# uc2C.net
KiCad netlist of a schematic drawn in Altium Designer
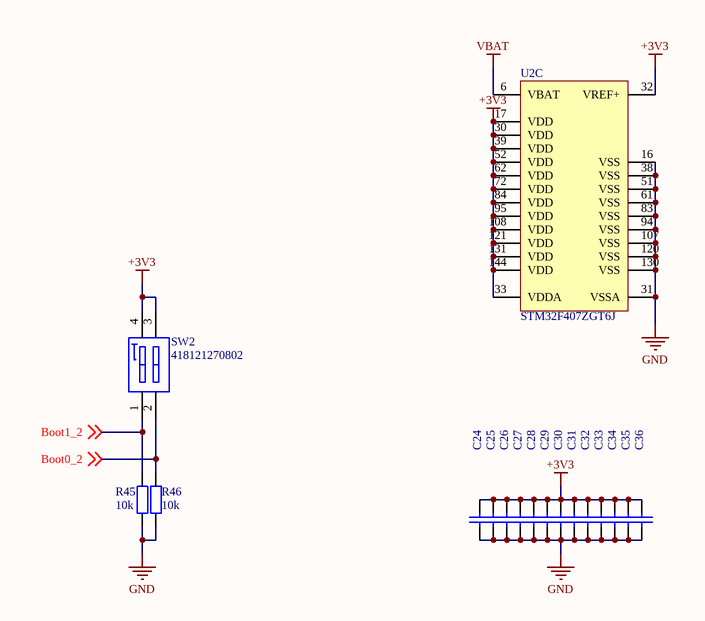
[diagram p0: uc2C.SchDoc]

(export (version "E")
  (design (tool "Eeschema 10.0.6"))
  (components
    (comp (ref "C24")
      (value "100nF")
      (footprint "C2012")
      (description "Capacitor")
      (fields
        (field (name "MANUFACTURER") "MULTICOMP")
        (field (name "MANUFACTURER PART NUMBER") "MC0805B104K500CT")
        (field (name "PUBLISHER") "Altium Limited")
      )
      (libsource (lib "Miscellaneous Devices") (part "Cap"))
    )
    (comp (ref "C25")
      (value "100nF")
      (footprint "C2012")
      (description "Capacitor")
      (fields
        (field (name "MANUFACTURER") "MULTICOMP")
        (field (name "MANUFACTURER PART NUMBER") "MC0805B104K500CT")
        (field (name "PUBLISHER") "Altium Limited")
      )
      (libsource (lib "Miscellaneous Devices") (part "Cap"))
    )
    (comp (ref "C26")
      (value "100nF")
      (footprint "C2012")
      (description "Capacitor")
      (fields
        (field (name "MANUFACTURER") "MULTICOMP")
        (field (name "MANUFACTURER PART NUMBER") "MC0805B104K500CT")
        (field (name "PUBLISHER") "Altium Limited")
      )
      (libsource (lib "Miscellaneous Devices") (part "Cap"))
    )
    (comp (ref "C27")
      (value "100nF")
      (footprint "C2012")
      (description "Capacitor")
      (fields
        (field (name "MANUFACTURER") "MULTICOMP")
        (field (name "MANUFACTURER PART NUMBER") "MC0805B104K500CT")
        (field (name "PUBLISHER") "Altium Limited")
      )
      (libsource (lib "Miscellaneous Devices") (part "Cap"))
    )
    (comp (ref "C28")
      (value "100nF")
      (footprint "C2012")
      (description "Capacitor")
      (fields
        (field (name "MANUFACTURER") "MULTICOMP")
        (field (name "MANUFACTURER PART NUMBER") "MC0805B104K500CT")
        (field (name "PUBLISHER") "Altium Limited")
      )
      (libsource (lib "Miscellaneous Devices") (part "Cap"))
    )
    (comp (ref "C29")
      (value "100nF")
      (footprint "C2012")
      (description "Capacitor")
      (fields
        (field (name "MANUFACTURER") "MULTICOMP")
        (field (name "MANUFACTURER PART NUMBER") "MC0805B104K500CT")
        (field (name "PUBLISHER") "Altium Limited")
      )
      (libsource (lib "Miscellaneous Devices") (part "Cap"))
    )
    (comp (ref "C30")
      (value "100nF")
      (footprint "C2012")
      (description "Capacitor")
      (fields
        (field (name "MANUFACTURER") "MULTICOMP")
        (field (name "MANUFACTURER PART NUMBER") "MC0805B104K500CT")
        (field (name "PUBLISHER") "Altium Limited")
      )
      (libsource (lib "Miscellaneous Devices") (part "Cap"))
    )
    (comp (ref "C31")
      (value "100nF")
      (footprint "C2012")
      (description "Capacitor")
      (fields
        (field (name "MANUFACTURER") "MULTICOMP")
        (field (name "MANUFACTURER PART NUMBER") "MC0805B104K500CT")
        (field (name "PUBLISHER") "Altium Limited")
      )
      (libsource (lib "Miscellaneous Devices") (part "Cap"))
    )
    (comp (ref "C32")
      (value "100nF")
      (footprint "C2012")
      (description "Capacitor")
      (fields
        (field (name "MANUFACTURER") "MULTICOMP")
        (field (name "MANUFACTURER PART NUMBER") "MC0805B104K500CT")
        (field (name "PUBLISHER") "Altium Limited")
      )
      (libsource (lib "Miscellaneous Devices") (part "Cap"))
    )
    (comp (ref "C33")
      (value "100nF")
      (footprint "C2012")
      (description "Capacitor")
      (fields
        (field (name "MANUFACTURER") "MULTICOMP")
        (field (name "MANUFACTURER PART NUMBER") "MC0805B104K500CT")
        (field (name "PUBLISHER") "Altium Limited")
      )
      (libsource (lib "Miscellaneous Devices") (part "Cap"))
    )
    (comp (ref "C34")
      (value "100nF")
      (footprint "C2012")
      (description "Capacitor")
      (fields
        (field (name "MANUFACTURER") "MULTICOMP")
        (field (name "MANUFACTURER PART NUMBER") "MC0805B104K500CT")
        (field (name "PUBLISHER") "Altium Limited")
      )
      (libsource (lib "Miscellaneous Devices") (part "Cap"))
    )
    (comp (ref "C35")
      (value "100nF")
      (footprint "C2012")
      (description "Capacitor")
      (fields
        (field (name "MANUFACTURER") "MULTICOMP")
        (field (name "MANUFACTURER PART NUMBER") "MC0805B104K500CT")
        (field (name "PUBLISHER") "Altium Limited")
      )
      (libsource (lib "Miscellaneous Devices") (part "Cap"))
    )
    (comp (ref "C36")
      (value "100nF")
      (footprint "C2012")
      (description "Capacitor")
      (fields
        (field (name "MANUFACTURER") "MULTICOMP")
        (field (name "MANUFACTURER PART NUMBER") "MC0805B104K500CT")
        (field (name "PUBLISHER") "Altium Limited")
      )
      (libsource (lib "Miscellaneous Devices") (part "Cap"))
    )
    (comp (ref "R45")
      (value "10k")
      (footprint "R2012")
      (description "Resistor")
      (fields
        (field (name "MANUFACTURER") "MULTICOMP")
        (field (name "MANUFACTURER PART NUMBER") "MC01W0805110K")
        (field (name "PUBLISHER") "Altium Limited")
      )
      (libsource (lib "") (part "Res2_1"))
    )
    (comp (ref "R46")
      (value "10k")
      (footprint "R2012")
      (description "Resistor")
      (fields
        (field (name "MANUFACTURER") "MULTICOMP")
        (field (name "MANUFACTURER PART NUMBER") "MC01W0805110K")
        (field (name "PUBLISHER") "Altium Limited")
      )
      (libsource (lib "Miscellaneous Devices") (part "Res2"))
    )
    (comp (ref "SW2")
      (value "418121270802")
      (footprint "418121270802")
      (description "WS-DISV 2.54 mm small compact SMD Dip Switch with raised actuator")
      (fields
        (field (name "MANUFACTURER") "Wuerth Elektronik")
        (field (name "MANUFACTURER PART NUMBER") "A6S2104H")
      )
      (libsource (lib "Altium Content Vault") (part "CMP-1438-00002-1"))
    )
    (comp (ref "U2")
      (value "STM32F407ZGT6J")
      (footprint "STM-LQFP144_M")
      (fields (field (name "MANUFACTURER") "STMicroelectronics"))
      (libsource (lib "Altium Content Vault") (part "CMP-0243-00063-2"))
    )
  )
  (nets
    (net (code "1") (name "+3V3") (class "Default")
      (node (ref "C24") (pin "2") (pinfunction "2_2") (pintype "passive"))
      (node (ref "C25") (pin "2") (pinfunction "2_2") (pintype "passive"))
      (node (ref "C26") (pin "2") (pinfunction "2_2") (pintype "passive"))
      (node (ref "C27") (pin "2") (pinfunction "2_2") (pintype "passive"))
      (node (ref "C28") (pin "2") (pinfunction "2_2") (pintype "passive"))
      (node (ref "C29") (pin "2") (pinfunction "2_2") (pintype "passive"))
      (node (ref "C30") (pin "2") (pinfunction "2_2") (pintype "passive"))
      (node (ref "C31") (pin "2") (pinfunction "2_2") (pintype "passive"))
      (node (ref "C32") (pin "2") (pinfunction "2_2") (pintype "passive"))
      (node (ref "C33") (pin "2") (pinfunction "2_2") (pintype "passive"))
      (node (ref "C34") (pin "2") (pinfunction "2_2") (pintype "passive"))
      (node (ref "C35") (pin "2") (pinfunction "2_2") (pintype "passive"))
      (node (ref "C36") (pin "2") (pinfunction "2_2") (pintype "passive"))
      (node (ref "SW2") (pin "3") (pinfunction "3_3") (pintype "passive"))
      (node (ref "SW2") (pin "4") (pinfunction "4_4") (pintype "passive"))
      (node (ref "U2") (pin "108") (pinfunction "VDD_108") (pintype "power_in"))
      (node (ref "U2") (pin "121") (pinfunction "VDD_121") (pintype "power_in"))
      (node (ref "U2") (pin "131") (pinfunction "VDD_131") (pintype "power_in"))
      (node (ref "U2") (pin "144") (pinfunction "VDD_144") (pintype "power_in"))
      (node (ref "U2") (pin "17") (pinfunction "VDD_17") (pintype "power_in"))
      (node (ref "U2") (pin "30") (pinfunction "VDD_30") (pintype "power_in"))
      (node (ref "U2") (pin "32") (pinfunction "VREF+_32") (pintype "power_in"))
      (node (ref "U2") (pin "33") (pinfunction "VDDA_33") (pintype "power_in"))
      (node (ref "U2") (pin "39") (pinfunction "VDD_39") (pintype "power_in"))
      (node (ref "U2") (pin "52") (pinfunction "VDD_52") (pintype "power_in"))
      (node (ref "U2") (pin "62") (pinfunction "VDD_62") (pintype "power_in"))
      (node (ref "U2") (pin "72") (pinfunction "VDD_72") (pintype "power_in"))
      (node (ref "U2") (pin "84") (pinfunction "VDD_84") (pintype "power_in"))
      (node (ref "U2") (pin "95") (pinfunction "VDD_95") (pintype "power_in"))
    )
    (net (code "2") (name "Boot0_2") (class "Default")
      (node (ref "R46") (pin "2") (pinfunction "2_2") (pintype "passive"))
      (node (ref "SW2") (pin "2") (pinfunction "2_2") (pintype "passive"))
    )
    (net (code "3") (name "Boot1_2") (class "Default")
      (node (ref "R45") (pin "1") (pinfunction "1_1") (pintype "passive"))
      (node (ref "SW2") (pin "1") (pinfunction "1_1") (pintype "passive"))
    )
    (net (code "4") (name "GND") (class "Default")
      (node (ref "C24") (pin "1") (pinfunction "1_1") (pintype "passive"))
      (node (ref "C25") (pin "1") (pinfunction "1_1") (pintype "passive"))
      (node (ref "C26") (pin "1") (pinfunction "1_1") (pintype "passive"))
      (node (ref "C27") (pin "1") (pinfunction "1_1") (pintype "passive"))
      (node (ref "C28") (pin "1") (pinfunction "1_1") (pintype "passive"))
      (node (ref "C29") (pin "1") (pinfunction "1_1") (pintype "passive"))
      (node (ref "C30") (pin "1") (pinfunction "1_1") (pintype "passive"))
      (node (ref "C31") (pin "1") (pinfunction "1_1") (pintype "passive"))
      (node (ref "C32") (pin "1") (pinfunction "1_1") (pintype "passive"))
      (node (ref "C33") (pin "1") (pinfunction "1_1") (pintype "passive"))
      (node (ref "C34") (pin "1") (pinfunction "1_1") (pintype "passive"))
      (node (ref "C35") (pin "1") (pinfunction "1_1") (pintype "passive"))
      (node (ref "C36") (pin "1") (pinfunction "1_1") (pintype "passive"))
      (node (ref "R45") (pin "2") (pinfunction "2_2") (pintype "passive"))
      (node (ref "R46") (pin "1") (pinfunction "1_1") (pintype "passive"))
      (node (ref "U2") (pin "107") (pinfunction "VSS_107") (pintype "power_in"))
      (node (ref "U2") (pin "120") (pinfunction "VSS_120") (pintype "power_in"))
      (node (ref "U2") (pin "130") (pinfunction "VSS_130") (pintype "power_in"))
      (node (ref "U2") (pin "16") (pinfunction "VSS_16") (pintype "power_in"))
      (node (ref "U2") (pin "31") (pinfunction "VSSA_31") (pintype "power_in"))
      (node (ref "U2") (pin "38") (pinfunction "VSS_38") (pintype "power_in"))
      (node (ref "U2") (pin "51") (pinfunction "VSS_51") (pintype "power_in"))
      (node (ref "U2") (pin "61") (pinfunction "VSS_61") (pintype "power_in"))
      (node (ref "U2") (pin "83") (pinfunction "VSS_83") (pintype "power_in"))
      (node (ref "U2") (pin "94") (pinfunction "VSS_94") (pintype "power_in"))
    )
    (net (code "5") (name "VBAT") (class "Default")
      (node (ref "U2") (pin "6") (pinfunction "VBAT_6") (pintype "power_in"))
    )
  )
)
